# Laser_Array_Temp_High_BRD_V1_2.net
KiCad netlist of a schematic drawn in EAGLE
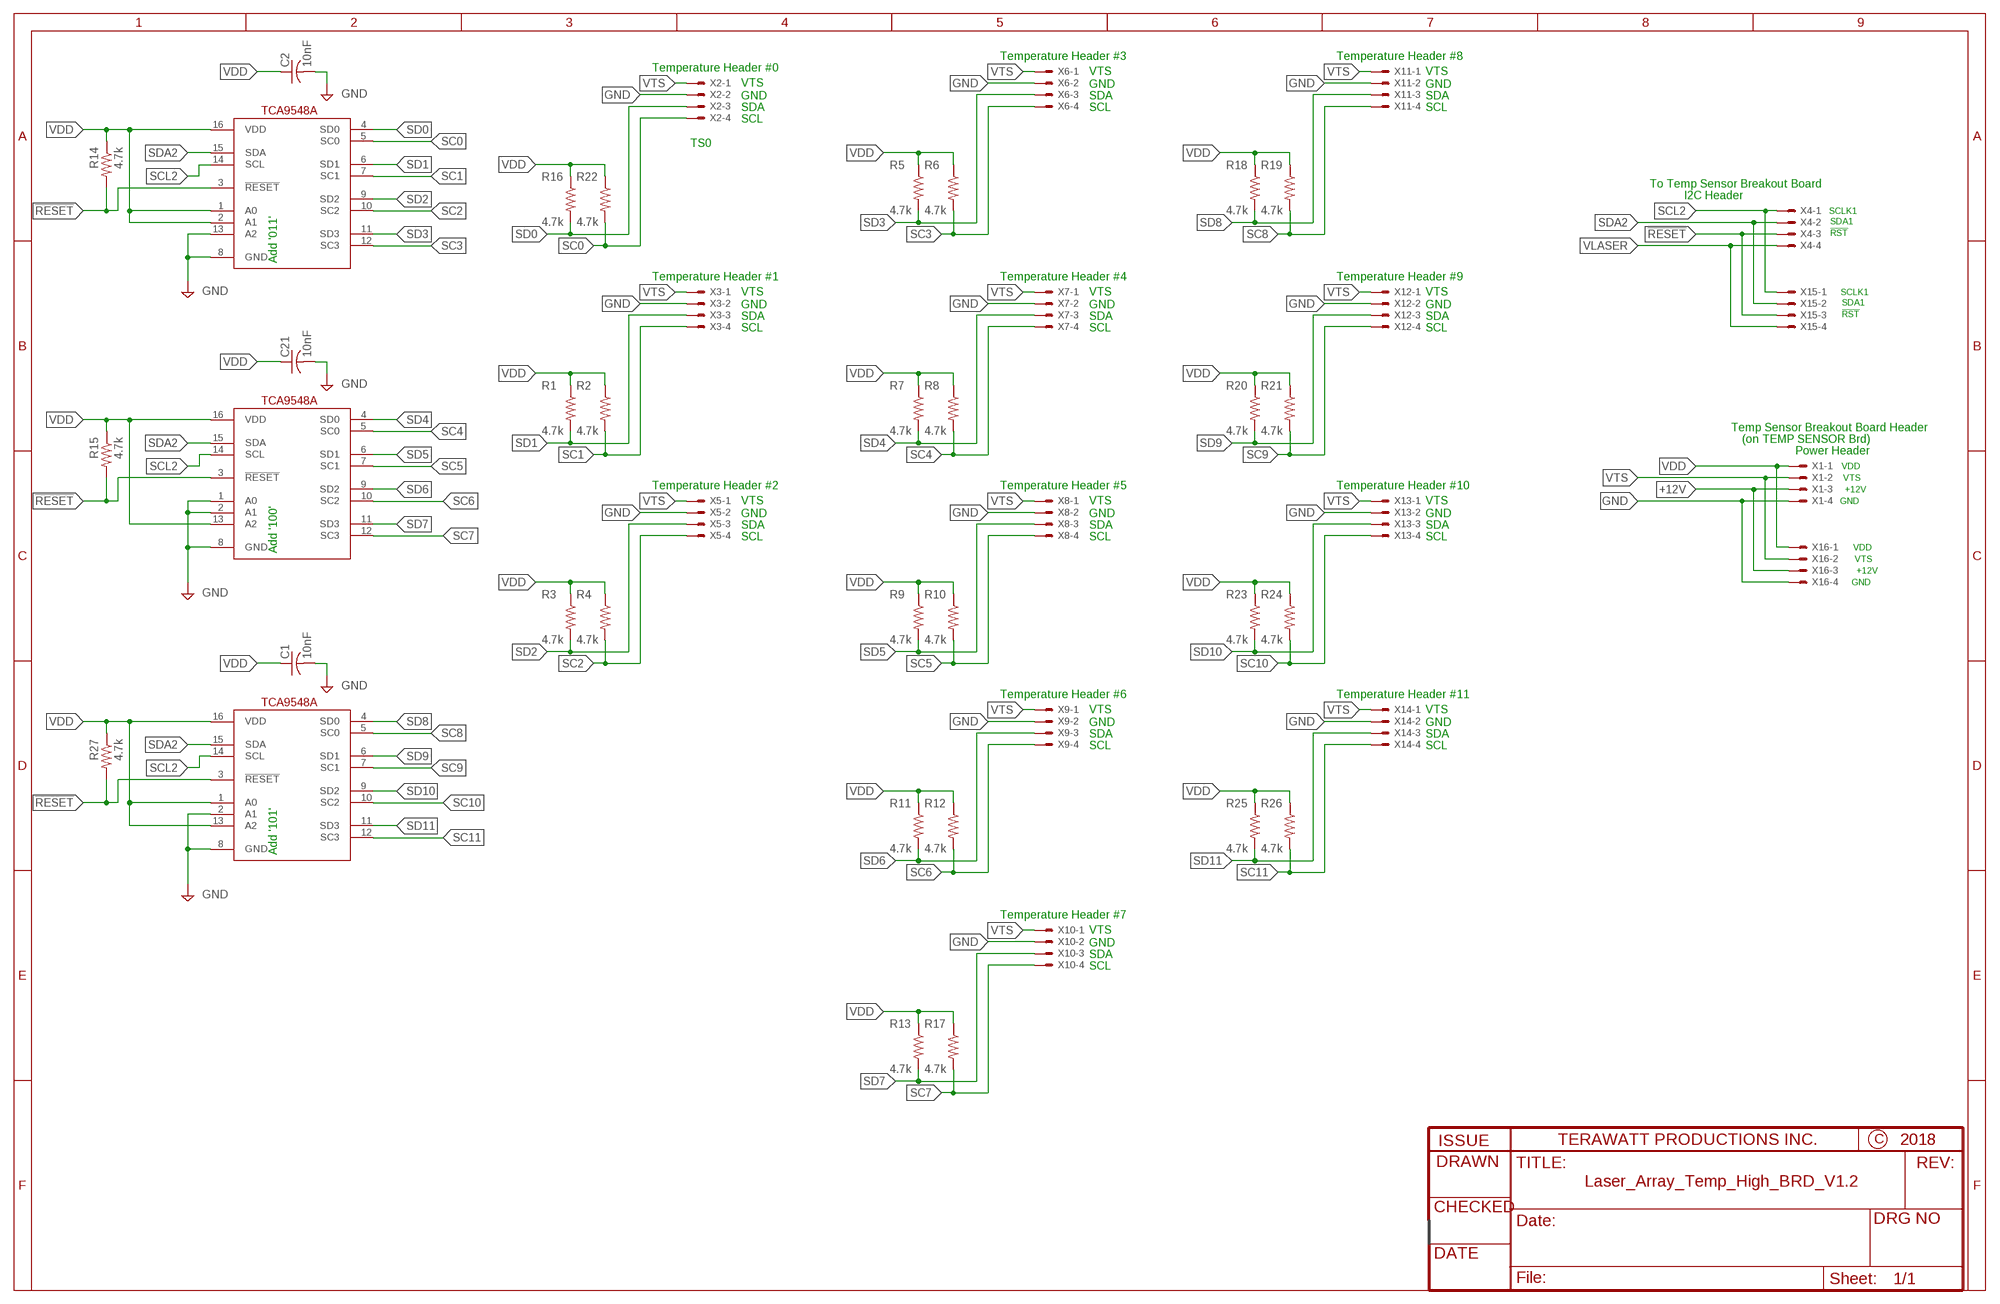
[diagram p0: schematic, sheet 1]

(export (version "E")
  (design (tool "Eeschema 10.0.6"))
  (components
    (comp (ref "C1")
      (value "10nF")
      (footprint "eagle-import:C0805")
      (libsource (lib "eagle-import") (part "C-USC0805"))
    )
    (comp (ref "C2")
      (value "10nF")
      (footprint "eagle-import:C0805")
      (libsource (lib "eagle-import") (part "C-USC0805"))
    )
    (comp (ref "C21")
      (value "10nF")
      (footprint "eagle-import:C0805")
      (libsource (lib "eagle-import") (part "C-USC0805"))
    )
    (comp (ref "R1")
      (value "4.7k")
      (footprint "eagle-import:M0805")
      (libsource (lib "eagle-import") (part "R-US_M0805"))
    )
    (comp (ref "R2")
      (value "4.7k")
      (footprint "eagle-import:M0805")
      (libsource (lib "eagle-import") (part "R-US_M0805"))
    )
    (comp (ref "R3")
      (value "4.7k")
      (footprint "eagle-import:M0805")
      (libsource (lib "eagle-import") (part "R-US_M0805"))
    )
    (comp (ref "R4")
      (value "4.7k")
      (footprint "eagle-import:M0805")
      (libsource (lib "eagle-import") (part "R-US_M0805"))
    )
    (comp (ref "R5")
      (value "4.7k")
      (footprint "eagle-import:M0805")
      (libsource (lib "eagle-import") (part "R-US_M0805"))
    )
    (comp (ref "R6")
      (value "4.7k")
      (footprint "eagle-import:M0805")
      (libsource (lib "eagle-import") (part "R-US_M0805"))
    )
    (comp (ref "R7")
      (value "4.7k")
      (footprint "eagle-import:M0805")
      (libsource (lib "eagle-import") (part "R-US_M0805"))
    )
    (comp (ref "R8")
      (value "4.7k")
      (footprint "eagle-import:M0805")
      (libsource (lib "eagle-import") (part "R-US_M0805"))
    )
    (comp (ref "R9")
      (value "4.7k")
      (footprint "eagle-import:M0805")
      (libsource (lib "eagle-import") (part "R-US_M0805"))
    )
    (comp (ref "R10")
      (value "4.7k")
      (footprint "eagle-import:M0805")
      (libsource (lib "eagle-import") (part "R-US_M0805"))
    )
    (comp (ref "R11")
      (value "4.7k")
      (footprint "eagle-import:M0805")
      (libsource (lib "eagle-import") (part "R-US_M0805"))
    )
    (comp (ref "R12")
      (value "4.7k")
      (footprint "eagle-import:M0805")
      (libsource (lib "eagle-import") (part "R-US_M0805"))
    )
    (comp (ref "R13")
      (value "4.7k")
      (footprint "eagle-import:M0805")
      (libsource (lib "eagle-import") (part "R-US_M0805"))
    )
    (comp (ref "R14")
      (value "4.7k")
      (footprint "eagle-import:M0805")
      (libsource (lib "eagle-import") (part "R-US_M0805"))
    )
    (comp (ref "R15")
      (value "4.7k")
      (footprint "eagle-import:M0805")
      (libsource (lib "eagle-import") (part "R-US_M0805"))
    )
    (comp (ref "R16")
      (value "4.7k")
      (footprint "eagle-import:M0805")
      (libsource (lib "eagle-import") (part "R-US_M0805"))
    )
    (comp (ref "R17")
      (value "4.7k")
      (footprint "eagle-import:M0805")
      (libsource (lib "eagle-import") (part "R-US_M0805"))
    )
    (comp (ref "R18")
      (value "4.7k")
      (footprint "eagle-import:M0805")
      (libsource (lib "eagle-import") (part "R-US_M0805"))
    )
    (comp (ref "R19")
      (value "4.7k")
      (footprint "eagle-import:M0805")
      (libsource (lib "eagle-import") (part "R-US_M0805"))
    )
    (comp (ref "R20")
      (value "4.7k")
      (footprint "eagle-import:M0805")
      (libsource (lib "eagle-import") (part "R-US_M0805"))
    )
    (comp (ref "R21")
      (value "4.7k")
      (footprint "eagle-import:M0805")
      (libsource (lib "eagle-import") (part "R-US_M0805"))
    )
    (comp (ref "R22")
      (value "4.7k")
      (footprint "eagle-import:M0805")
      (libsource (lib "eagle-import") (part "R-US_M0805"))
    )
    (comp (ref "R23")
      (value "4.7k")
      (footprint "eagle-import:M0805")
      (libsource (lib "eagle-import") (part "R-US_M0805"))
    )
    (comp (ref "R24")
      (value "4.7k")
      (footprint "eagle-import:M0805")
      (libsource (lib "eagle-import") (part "R-US_M0805"))
    )
    (comp (ref "R25")
      (value "4.7k")
      (footprint "eagle-import:M0805")
      (libsource (lib "eagle-import") (part "R-US_M0805"))
    )
    (comp (ref "R26")
      (value "4.7k")
      (footprint "eagle-import:M0805")
      (libsource (lib "eagle-import") (part "R-US_M0805"))
    )
    (comp (ref "R27")
      (value "4.7k")
      (footprint "eagle-import:M0805")
      (libsource (lib "eagle-import") (part "R-US_M0805"))
    )
    (comp (ref "U1")
      (value "TCA9546A")
      (footprint "eagle-import:SOIC16N")
      (libsource (lib "eagle-import") (part "TCA9546A"))
    )
    (comp (ref "U2")
      (value "TCA9546A")
      (footprint "eagle-import:SOIC16N")
      (libsource (lib "eagle-import") (part "TCA9546A"))
    )
    (comp (ref "U3")
      (value "TCA9546A")
      (footprint "eagle-import:SOIC16N")
      (libsource (lib "eagle-import") (part "TCA9546A"))
    )
    (comp (ref "X1")
      (value "22-23-2041")
      (footprint "eagle-import:22-23-2041")
      (fields (field (name "MF") "MOLEX"))
      (libsource (lib "eagle-import") (part "22-23-2041"))
    )
    (comp (ref "X2")
      (value "22-23-2041")
      (footprint "eagle-import:22-23-2041")
      (fields (field (name "MF") "MOLEX"))
      (libsource (lib "eagle-import") (part "22-23-2041"))
    )
    (comp (ref "X3")
      (value "22-23-2041")
      (footprint "eagle-import:22-23-2041")
      (fields (field (name "MF") "MOLEX"))
      (libsource (lib "eagle-import") (part "22-23-2041"))
    )
    (comp (ref "X4")
      (value "22-23-2041")
      (footprint "eagle-import:22-23-2041")
      (fields (field (name "MF") "MOLEX"))
      (libsource (lib "eagle-import") (part "22-23-2041"))
    )
    (comp (ref "X5")
      (value "22-23-2041")
      (footprint "eagle-import:22-23-2041")
      (fields (field (name "MF") "MOLEX"))
      (libsource (lib "eagle-import") (part "22-23-2041"))
    )
    (comp (ref "X6")
      (value "22-23-2041")
      (footprint "eagle-import:22-23-2041")
      (fields (field (name "MF") "MOLEX"))
      (libsource (lib "eagle-import") (part "22-23-2041"))
    )
    (comp (ref "X7")
      (value "22-23-2041")
      (footprint "eagle-import:22-23-2041")
      (fields (field (name "MF") "MOLEX"))
      (libsource (lib "eagle-import") (part "22-23-2041"))
    )
    (comp (ref "X8")
      (value "22-23-2041")
      (footprint "eagle-import:22-23-2041")
      (fields (field (name "MF") "MOLEX"))
      (libsource (lib "eagle-import") (part "22-23-2041"))
    )
    (comp (ref "X9")
      (value "22-23-2041")
      (footprint "eagle-import:22-23-2041")
      (fields (field (name "MF") "MOLEX"))
      (libsource (lib "eagle-import") (part "22-23-2041"))
    )
    (comp (ref "X10")
      (value "22-23-2041")
      (footprint "eagle-import:22-23-2041")
      (fields (field (name "MF") "MOLEX"))
      (libsource (lib "eagle-import") (part "22-23-2041"))
    )
    (comp (ref "X11")
      (value "22-23-2041")
      (footprint "eagle-import:22-23-2041")
      (fields (field (name "MF") "MOLEX"))
      (libsource (lib "eagle-import") (part "22-23-2041"))
    )
    (comp (ref "X12")
      (value "22-23-2041")
      (footprint "eagle-import:22-23-2041")
      (fields (field (name "MF") "MOLEX"))
      (libsource (lib "eagle-import") (part "22-23-2041"))
    )
    (comp (ref "X13")
      (value "22-23-2041")
      (footprint "eagle-import:22-23-2041")
      (fields (field (name "MF") "MOLEX"))
      (libsource (lib "eagle-import") (part "22-23-2041"))
    )
    (comp (ref "X14")
      (value "22-23-2041")
      (footprint "eagle-import:22-23-2041")
      (fields (field (name "MF") "MOLEX"))
      (libsource (lib "eagle-import") (part "22-23-2041"))
    )
    (comp (ref "X15")
      (value "22-23-2041")
      (footprint "eagle-import:22-23-2041")
      (fields (field (name "MF") "MOLEX"))
      (libsource (lib "eagle-import") (part "22-23-2041"))
    )
    (comp (ref "X16")
      (value "22-23-2041")
      (footprint "eagle-import:22-23-2041")
      (fields (field (name "MF") "MOLEX"))
      (libsource (lib "eagle-import") (part "22-23-2041"))
    )
  )
  (nets
    (net (code "1") (name "+12V") (class "Default")
      (node (ref "X1") (pin "3") (pinfunction "S_3") (pintype "passive"))
      (node (ref "X16") (pin "3") (pinfunction "S_3") (pintype "passive"))
    )
    (net (code "2") (name "/~{RESET}") (class "Default")
      (node (ref "R14") (pin "2") (pinfunction "2_2") (pintype "passive"))
      (node (ref "R15") (pin "2") (pinfunction "2_2") (pintype "passive"))
      (node (ref "R27") (pin "2") (pinfunction "2_2") (pintype "passive"))
      (node (ref "U1") (pin "3") (pinfunction "~{RESET}_3") (pintype "bidirectional"))
      (node (ref "U2") (pin "3") (pinfunction "~{RESET}_3") (pintype "bidirectional"))
      (node (ref "U3") (pin "3") (pinfunction "~{RESET}_3") (pintype "bidirectional"))
      (node (ref "X15") (pin "3") (pinfunction "S_3") (pintype "passive"))
      (node (ref "X4") (pin "3") (pinfunction "S_3") (pintype "passive"))
    )
    (net (code "3") (name "GND") (class "Default")
      (node (ref "C1") (pin "2") (pinfunction "2_2") (pintype "passive"))
      (node (ref "C2") (pin "2") (pinfunction "2_2") (pintype "passive"))
      (node (ref "C21") (pin "2") (pinfunction "2_2") (pintype "passive"))
      (node (ref "U1") (pin "13") (pinfunction "A2_13") (pintype "bidirectional"))
      (node (ref "U1") (pin "8") (pinfunction "GND_8") (pintype "bidirectional"))
      (node (ref "U2") (pin "1") (pinfunction "A0_1") (pintype "bidirectional"))
      (node (ref "U2") (pin "2") (pinfunction "A1_2") (pintype "bidirectional"))
      (node (ref "U2") (pin "8") (pinfunction "GND_8") (pintype "bidirectional"))
      (node (ref "U3") (pin "2") (pinfunction "A1_2") (pintype "bidirectional"))
      (node (ref "U3") (pin "8") (pinfunction "GND_8") (pintype "bidirectional"))
      (node (ref "X1") (pin "4") (pinfunction "S_4") (pintype "passive"))
      (node (ref "X10") (pin "2") (pinfunction "S_2") (pintype "passive"))
      (node (ref "X11") (pin "2") (pinfunction "S_2") (pintype "passive"))
      (node (ref "X12") (pin "2") (pinfunction "S_2") (pintype "passive"))
      (node (ref "X13") (pin "2") (pinfunction "S_2") (pintype "passive"))
      (node (ref "X14") (pin "2") (pinfunction "S_2") (pintype "passive"))
      (node (ref "X16") (pin "4") (pinfunction "S_4") (pintype "passive"))
      (node (ref "X2") (pin "2") (pinfunction "S_2") (pintype "passive"))
      (node (ref "X3") (pin "2") (pinfunction "S_2") (pintype "passive"))
      (node (ref "X5") (pin "2") (pinfunction "S_2") (pintype "passive"))
      (node (ref "X6") (pin "2") (pinfunction "S_2") (pintype "passive"))
      (node (ref "X7") (pin "2") (pinfunction "S_2") (pintype "passive"))
      (node (ref "X8") (pin "2") (pinfunction "S_2") (pintype "passive"))
      (node (ref "X9") (pin "2") (pinfunction "S_2") (pintype "passive"))
    )
    (net (code "4") (name "SC0") (class "Default")
      (node (ref "R22") (pin "2") (pinfunction "2_2") (pintype "passive"))
      (node (ref "U1") (pin "5") (pinfunction "SC0_5") (pintype "bidirectional"))
      (node (ref "X2") (pin "4") (pinfunction "S_4") (pintype "passive"))
    )
    (net (code "5") (name "SC1") (class "Default")
      (node (ref "R2") (pin "2") (pinfunction "2_2") (pintype "passive"))
      (node (ref "U1") (pin "7") (pinfunction "SC1_7") (pintype "bidirectional"))
      (node (ref "X3") (pin "4") (pinfunction "S_4") (pintype "passive"))
    )
    (net (code "6") (name "SC2") (class "Default")
      (node (ref "R4") (pin "2") (pinfunction "2_2") (pintype "passive"))
      (node (ref "U1") (pin "10") (pinfunction "SC2_10") (pintype "bidirectional"))
      (node (ref "X5") (pin "4") (pinfunction "S_4") (pintype "passive"))
    )
    (net (code "7") (name "SC3") (class "Default")
      (node (ref "R6") (pin "2") (pinfunction "2_2") (pintype "passive"))
      (node (ref "U1") (pin "12") (pinfunction "SC3_12") (pintype "bidirectional"))
      (node (ref "X6") (pin "4") (pinfunction "S_4") (pintype "passive"))
    )
    (net (code "8") (name "SC4") (class "Default")
      (node (ref "R8") (pin "2") (pinfunction "2_2") (pintype "passive"))
      (node (ref "U2") (pin "5") (pinfunction "SC0_5") (pintype "bidirectional"))
      (node (ref "X7") (pin "4") (pinfunction "S_4") (pintype "passive"))
    )
    (net (code "9") (name "SC5") (class "Default")
      (node (ref "R10") (pin "2") (pinfunction "2_2") (pintype "passive"))
      (node (ref "U2") (pin "7") (pinfunction "SC1_7") (pintype "bidirectional"))
      (node (ref "X8") (pin "4") (pinfunction "S_4") (pintype "passive"))
    )
    (net (code "10") (name "SC6") (class "Default")
      (node (ref "R12") (pin "2") (pinfunction "2_2") (pintype "passive"))
      (node (ref "U2") (pin "10") (pinfunction "SC2_10") (pintype "bidirectional"))
      (node (ref "X9") (pin "4") (pinfunction "S_4") (pintype "passive"))
    )
    (net (code "11") (name "SC7") (class "Default")
      (node (ref "R17") (pin "2") (pinfunction "2_2") (pintype "passive"))
      (node (ref "U2") (pin "12") (pinfunction "SC3_12") (pintype "bidirectional"))
      (node (ref "X10") (pin "4") (pinfunction "S_4") (pintype "passive"))
    )
    (net (code "12") (name "SC8") (class "Default")
      (node (ref "R19") (pin "2") (pinfunction "2_2") (pintype "passive"))
      (node (ref "U3") (pin "5") (pinfunction "SC0_5") (pintype "bidirectional"))
      (node (ref "X11") (pin "4") (pinfunction "S_4") (pintype "passive"))
    )
    (net (code "13") (name "SC9") (class "Default")
      (node (ref "R21") (pin "2") (pinfunction "2_2") (pintype "passive"))
      (node (ref "U3") (pin "7") (pinfunction "SC1_7") (pintype "bidirectional"))
      (node (ref "X12") (pin "4") (pinfunction "S_4") (pintype "passive"))
    )
    (net (code "14") (name "SC10") (class "Default")
      (node (ref "R24") (pin "2") (pinfunction "2_2") (pintype "passive"))
      (node (ref "U3") (pin "10") (pinfunction "SC2_10") (pintype "bidirectional"))
      (node (ref "X13") (pin "4") (pinfunction "S_4") (pintype "passive"))
    )
    (net (code "15") (name "SC11") (class "Default")
      (node (ref "R26") (pin "2") (pinfunction "2_2") (pintype "passive"))
      (node (ref "U3") (pin "12") (pinfunction "SC3_12") (pintype "bidirectional"))
      (node (ref "X14") (pin "4") (pinfunction "S_4") (pintype "passive"))
    )
    (net (code "16") (name "SCL2") (class "Default")
      (node (ref "U1") (pin "14") (pinfunction "SCL_14") (pintype "bidirectional"))
      (node (ref "U2") (pin "14") (pinfunction "SCL_14") (pintype "bidirectional"))
      (node (ref "U3") (pin "14") (pinfunction "SCL_14") (pintype "bidirectional"))
      (node (ref "X15") (pin "1") (pinfunction "S_1") (pintype "passive"))
      (node (ref "X4") (pin "1") (pinfunction "S_1") (pintype "passive"))
    )
    (net (code "17") (name "SD0") (class "Default")
      (node (ref "R16") (pin "2") (pinfunction "2_2") (pintype "passive"))
      (node (ref "U1") (pin "4") (pinfunction "SD0_4") (pintype "bidirectional"))
      (node (ref "X2") (pin "3") (pinfunction "S_3") (pintype "passive"))
    )
    (net (code "18") (name "SD1") (class "Default")
      (node (ref "R1") (pin "2") (pinfunction "2_2") (pintype "passive"))
      (node (ref "U1") (pin "6") (pinfunction "SD1_6") (pintype "bidirectional"))
      (node (ref "X3") (pin "3") (pinfunction "S_3") (pintype "passive"))
    )
    (net (code "19") (name "SD2") (class "Default")
      (node (ref "R3") (pin "2") (pinfunction "2_2") (pintype "passive"))
      (node (ref "U1") (pin "9") (pinfunction "SD2_9") (pintype "bidirectional"))
      (node (ref "X5") (pin "3") (pinfunction "S_3") (pintype "passive"))
    )
    (net (code "20") (name "SD3") (class "Default")
      (node (ref "R5") (pin "2") (pinfunction "2_2") (pintype "passive"))
      (node (ref "U1") (pin "11") (pinfunction "SD3_11") (pintype "bidirectional"))
      (node (ref "X6") (pin "3") (pinfunction "S_3") (pintype "passive"))
    )
    (net (code "21") (name "SD4") (class "Default")
      (node (ref "R7") (pin "2") (pinfunction "2_2") (pintype "passive"))
      (node (ref "U2") (pin "4") (pinfunction "SD0_4") (pintype "bidirectional"))
      (node (ref "X7") (pin "3") (pinfunction "S_3") (pintype "passive"))
    )
    (net (code "22") (name "SD5") (class "Default")
      (node (ref "R9") (pin "2") (pinfunction "2_2") (pintype "passive"))
      (node (ref "U2") (pin "6") (pinfunction "SD1_6") (pintype "bidirectional"))
      (node (ref "X8") (pin "3") (pinfunction "S_3") (pintype "passive"))
    )
    (net (code "23") (name "SD6") (class "Default")
      (node (ref "R11") (pin "2") (pinfunction "2_2") (pintype "passive"))
      (node (ref "U2") (pin "9") (pinfunction "SD2_9") (pintype "bidirectional"))
      (node (ref "X9") (pin "3") (pinfunction "S_3") (pintype "passive"))
    )
    (net (code "24") (name "SD7") (class "Default")
      (node (ref "R13") (pin "2") (pinfunction "2_2") (pintype "passive"))
      (node (ref "U2") (pin "11") (pinfunction "SD3_11") (pintype "bidirectional"))
      (node (ref "X10") (pin "3") (pinfunction "S_3") (pintype "passive"))
    )
    (net (code "25") (name "SD8") (class "Default")
      (node (ref "R18") (pin "2") (pinfunction "2_2") (pintype "passive"))
      (node (ref "U3") (pin "4") (pinfunction "SD0_4") (pintype "bidirectional"))
      (node (ref "X11") (pin "3") (pinfunction "S_3") (pintype "passive"))
    )
    (net (code "26") (name "SD9") (class "Default")
      (node (ref "R20") (pin "2") (pinfunction "2_2") (pintype "passive"))
      (node (ref "U3") (pin "6") (pinfunction "SD1_6") (pintype "bidirectional"))
      (node (ref "X12") (pin "3") (pinfunction "S_3") (pintype "passive"))
    )
    (net (code "27") (name "SD10") (class "Default")
      (node (ref "R23") (pin "2") (pinfunction "2_2") (pintype "passive"))
      (node (ref "U3") (pin "9") (pinfunction "SD2_9") (pintype "bidirectional"))
      (node (ref "X13") (pin "3") (pinfunction "S_3") (pintype "passive"))
    )
    (net (code "28") (name "SD11") (class "Default")
      (node (ref "R25") (pin "2") (pinfunction "2_2") (pintype "passive"))
      (node (ref "U3") (pin "11") (pinfunction "SD3_11") (pintype "bidirectional"))
      (node (ref "X14") (pin "3") (pinfunction "S_3") (pintype "passive"))
    )
    (net (code "29") (name "SDA2") (class "Default")
      (node (ref "U1") (pin "15") (pinfunction "SDA_15") (pintype "bidirectional"))
      (node (ref "U2") (pin "15") (pinfunction "SDA_15") (pintype "bidirectional"))
      (node (ref "U3") (pin "15") (pinfunction "SDA_15") (pintype "bidirectional"))
      (node (ref "X15") (pin "2") (pinfunction "S_2") (pintype "passive"))
      (node (ref "X4") (pin "2") (pinfunction "S_2") (pintype "passive"))
    )
    (net (code "30") (name "VDD") (class "Default")
      (node (ref "C1") (pin "1") (pinfunction "1_1") (pintype "passive"))
      (node (ref "C2") (pin "1") (pinfunction "1_1") (pintype "passive"))
      (node (ref "C21") (pin "1") (pinfunction "1_1") (pintype "passive"))
      (node (ref "R1") (pin "1") (pinfunction "1_1") (pintype "passive"))
      (node (ref "R10") (pin "1") (pinfunction "1_1") (pintype "passive"))
      (node (ref "R11") (pin "1") (pinfunction "1_1") (pintype "passive"))
      (node (ref "R12") (pin "1") (pinfunction "1_1") (pintype "passive"))
      (node (ref "R13") (pin "1") (pinfunction "1_1") (pintype "passive"))
      (node (ref "R14") (pin "1") (pinfunction "1_1") (pintype "passive"))
      (node (ref "R15") (pin "1") (pinfunction "1_1") (pintype "passive"))
      (node (ref "R16") (pin "1") (pinfunction "1_1") (pintype "passive"))
      (node (ref "R17") (pin "1") (pinfunction "1_1") (pintype "passive"))
      (node (ref "R18") (pin "1") (pinfunction "1_1") (pintype "passive"))
      (node (ref "R19") (pin "1") (pinfunction "1_1") (pintype "passive"))
      (node (ref "R2") (pin "1") (pinfunction "1_1") (pintype "passive"))
      (node (ref "R20") (pin "1") (pinfunction "1_1") (pintype "passive"))
      (node (ref "R21") (pin "1") (pinfunction "1_1") (pintype "passive"))
      (node (ref "R22") (pin "1") (pinfunction "1_1") (pintype "passive"))
      (node (ref "R23") (pin "1") (pinfunction "1_1") (pintype "passive"))
      (node (ref "R24") (pin "1") (pinfunction "1_1") (pintype "passive"))
      (node (ref "R25") (pin "1") (pinfunction "1_1") (pintype "passive"))
      (node (ref "R26") (pin "1") (pinfunction "1_1") (pintype "passive"))
      (node (ref "R27") (pin "1") (pinfunction "1_1") (pintype "passive"))
      (node (ref "R3") (pin "1") (pinfunction "1_1") (pintype "passive"))
      (node (ref "R4") (pin "1") (pinfunction "1_1") (pintype "passive"))
      (node (ref "R5") (pin "1") (pinfunction "1_1") (pintype "passive"))
      (node (ref "R6") (pin "1") (pinfunction "1_1") (pintype "passive"))
      (node (ref "R7") (pin "1") (pinfunction "1_1") (pintype "passive"))
      (node (ref "R8") (pin "1") (pinfunction "1_1") (pintype "passive"))
      (node (ref "R9") (pin "1") (pinfunction "1_1") (pintype "passive"))
      (node (ref "U1") (pin "1") (pinfunction "A0_1") (pintype "bidirectional"))
      (node (ref "U1") (pin "16") (pinfunction "VDD_16") (pintype "bidirectional"))
      (node (ref "U1") (pin "2") (pinfunction "A1_2") (pintype "bidirectional"))
      (node (ref "U2") (pin "13") (pinfunction "A2_13") (pintype "bidirectional"))
      (node (ref "U2") (pin "16") (pinfunction "VDD_16") (pintype "bidirectional"))
      (node (ref "U3") (pin "1") (pinfunction "A0_1") (pintype "bidirectional"))
      (node (ref "U3") (pin "13") (pinfunction "A2_13") (pintype "bidirectional"))
      (node (ref "U3") (pin "16") (pinfunction "VDD_16") (pintype "bidirectional"))
      (node (ref "X1") (pin "1") (pinfunction "S_1") (pintype "passive"))
      (node (ref "X16") (pin "1") (pinfunction "S_1") (pintype "passive"))
    )
    (net (code "31") (name "VLASER") (class "Default")
      (node (ref "X15") (pin "4") (pinfunction "S_4") (pintype "passive"))
      (node (ref "X4") (pin "4") (pinfunction "S_4") (pintype "passive"))
    )
    (net (code "32") (name "VTS") (class "Default")
      (node (ref "X1") (pin "2") (pinfunction "S_2") (pintype "passive"))
      (node (ref "X10") (pin "1") (pinfunction "S_1") (pintype "passive"))
      (node (ref "X11") (pin "1") (pinfunction "S_1") (pintype "passive"))
      (node (ref "X12") (pin "1") (pinfunction "S_1") (pintype "passive"))
      (node (ref "X13") (pin "1") (pinfunction "S_1") (pintype "passive"))
      (node (ref "X14") (pin "1") (pinfunction "S_1") (pintype "passive"))
      (node (ref "X16") (pin "2") (pinfunction "S_2") (pintype "passive"))
      (node (ref "X2") (pin "1") (pinfunction "S_1") (pintype "passive"))
      (node (ref "X3") (pin "1") (pinfunction "S_1") (pintype "passive"))
      (node (ref "X5") (pin "1") (pinfunction "S_1") (pintype "passive"))
      (node (ref "X6") (pin "1") (pinfunction "S_1") (pintype "passive"))
      (node (ref "X7") (pin "1") (pinfunction "S_1") (pintype "passive"))
      (node (ref "X8") (pin "1") (pinfunction "S_1") (pintype "passive"))
      (node (ref "X9") (pin "1") (pinfunction "S_1") (pintype "passive"))
    )
  )
)
